# mach-relay.net
KiCad netlist of a schematic drawn in Altium Designer
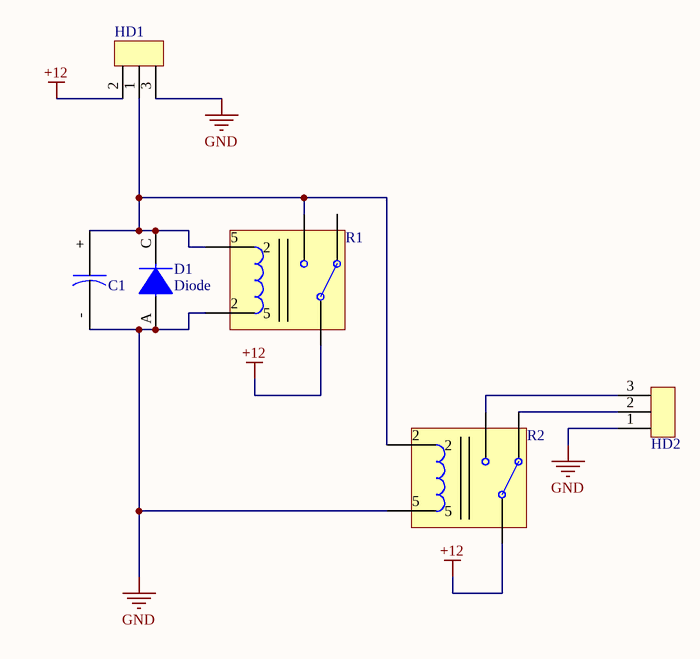
[diagram p0: mach-relay.SchDoc]

(export (version "E")
  (design (tool "Eeschema 10.0.6"))
  (components
    (comp (ref "C1")
      (value "Pol-Cap")
      (footprint "POL_250mil")
      (description "Tụ điện phân cực")
      (libsource (lib "LuongTanDat") (part "Pol-Cap"))
    )
    (comp (ref "D1")
      (value "Diode")
      (footprint "DIODE - VERTICAL")
      (libsource (lib "LuongTanDat") (part "Diode"))
    )
    (comp (ref "HD1") (value "HD_3") (footprint "HEADER_3") (libsource (lib "LuongTanDat") (part "HD_3")))
    (comp (ref "HD2") (value "HD_3") (footprint "HEADER_3") (libsource (lib "") (part "HD_3_1")))
    (comp (ref "R1")
      (value "Relay_5pin")
      (footprint "RELAY-5PIN")
      (libsource (lib "LuongTanDat") (part "Relay_5pin"))
    )
    (comp (ref "R2") (value "Relay_5pin") (footprint "RELAY-5PIN") (libsource (lib "") (part "Relay_5pin_1")))
  )
  (nets
    (net (code "1") (name "+12") (class "Default")
      (node (ref "HD1") (pin "2") (pinfunction "2_2") (pintype "passive"))
      (node (ref "R1") (pin "1") (pinfunction "1_1") (pintype "passive"))
      (node (ref "R2") (pin "1") (pinfunction "1_1") (pintype "passive"))
    )
    (net (code "2") (name "GND") (class "Default")
      (node (ref "C1") (pin "-") (pintype "passive"))
      (node (ref "D1") (pin "A") (pinfunction "1_A") (pintype "passive"))
      (node (ref "HD1") (pin "3") (pinfunction "3_3") (pintype "passive"))
      (node (ref "HD2") (pin "1") (pinfunction "1_1") (pintype "passive"))
      (node (ref "R1") (pin "2") (pinfunction "5_2") (pintype "passive"))
      (node (ref "R2") (pin "5") (pinfunction "5_5") (pintype "passive"))
    )
    (net (code "3") (name "Net-(D1-2)") (class "Default")
      (node (ref "C1") (pin "+") (pintype "passive"))
      (node (ref "D1") (pin "C") (pinfunction "2_C") (pintype "passive"))
      (node (ref "HD1") (pin "1") (pinfunction "1_1") (pintype "passive"))
      (node (ref "R1") (pin "3") (pinfunction "3_3") (pintype "passive"))
      (node (ref "R1") (pin "5") (pinfunction "2_5") (pintype "passive"))
      (node (ref "R2") (pin "2") (pinfunction "2_2") (pintype "passive"))
    )
    (net (code "4") (name "Net-(HD2-Pad2)") (class "Default")
      (node (ref "HD2") (pin "2") (pinfunction "2_2") (pintype "passive"))
      (node (ref "R2") (pin "4") (pinfunction "4_4") (pintype "passive"))
    )
    (net (code "5") (name "Net-(HD2-Pad3)") (class "Default")
      (node (ref "HD2") (pin "3") (pinfunction "3_3") (pintype "passive"))
      (node (ref "R2") (pin "3") (pinfunction "3_3") (pintype "passive"))
    )
    (net (code "6") (name "unconnected-(R1-Pad4)") (class "Default")
      (node (ref "R1") (pin "4") (pinfunction "4_4") (pintype "passive"))
    )
  )
)
